# scoutmakes_robot_kit.net
KiCad netlist of a schematic drawn in EAGLE
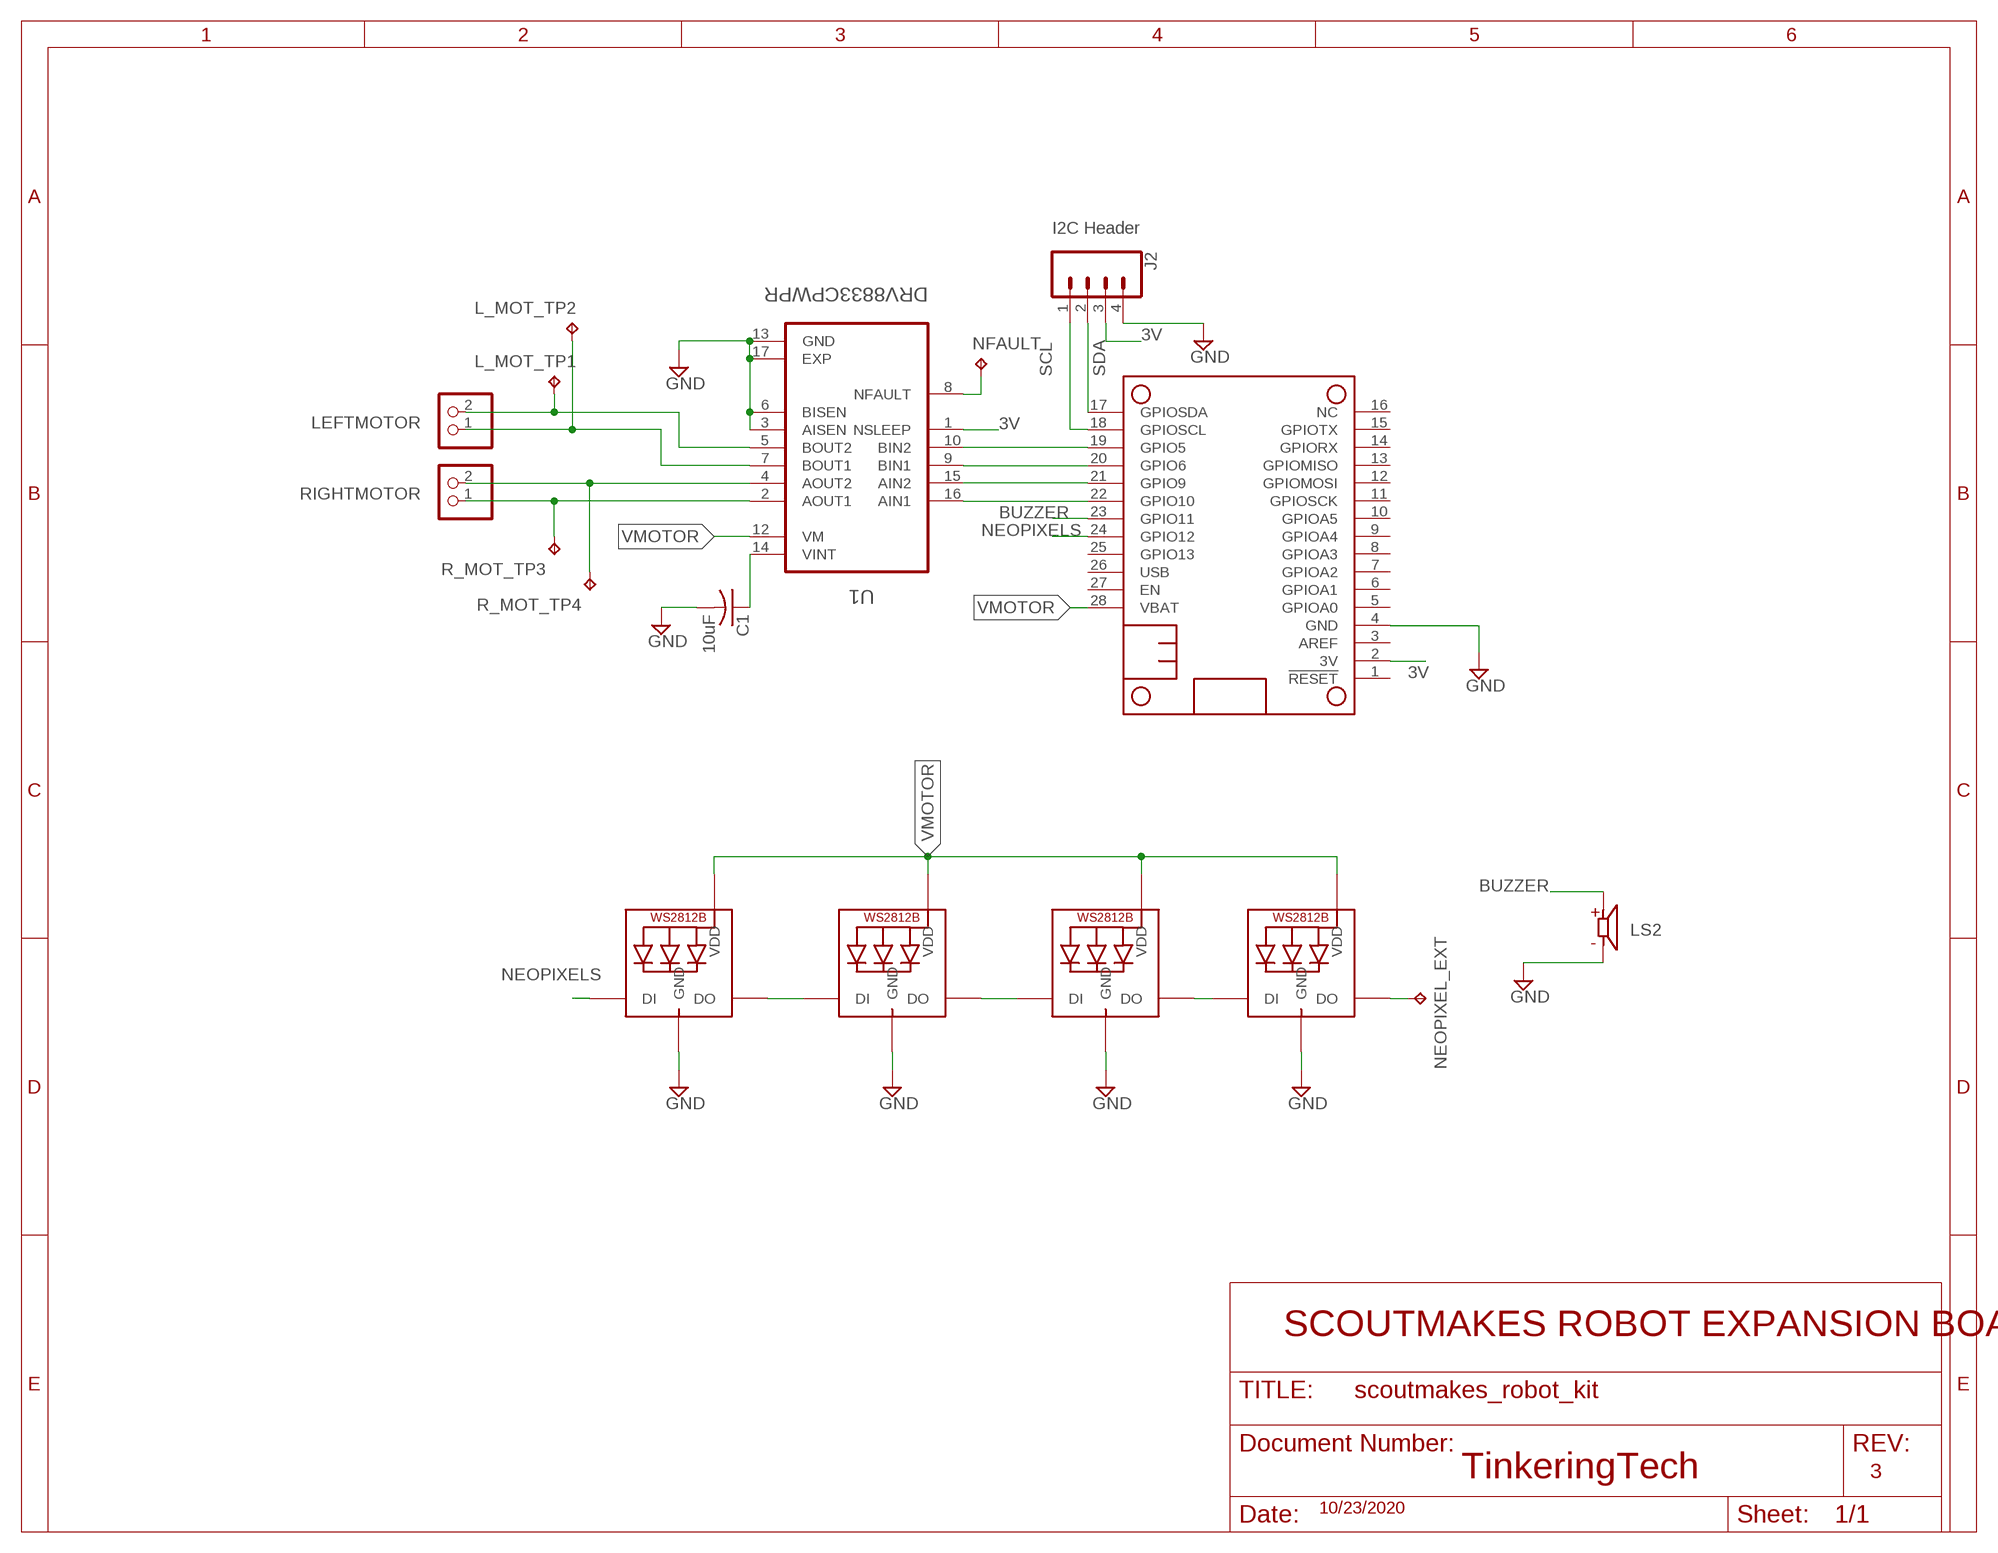
[diagram p0: schematic, sheet 1]

(export (version "E")
  (design (tool "Eeschema 10.0.6"))
  (components
    (comp (ref "C1")
      (value "10uF")
      (footprint "eagle-import:C0805")
      (libsource (lib "eagle-import") (part "C-USC0805"))
    )
    (comp (ref "J2")
      (value "CONN_04")
      (footprint "eagle-import:1X04")
      (libsource (lib "eagle-import") (part "CONN_04"))
    )
    (comp (ref "LED1")
      (value "WS2812B_4020")
      (footprint "eagle-import:WS2812B_4020")
      (libsource (lib "eagle-import") (part "WS2812B_4020"))
    )
    (comp (ref "LED2")
      (value "WS2812B_4020")
      (footprint "eagle-import:WS2812B_4020")
      (libsource (lib "eagle-import") (part "WS2812B_4020"))
    )
    (comp (ref "LED3")
      (value "WS2812B_4020")
      (footprint "eagle-import:WS2812B_4020")
      (libsource (lib "eagle-import") (part "WS2812B_4020"))
    )
    (comp (ref "LED4")
      (value "WS2812B_4020")
      (footprint "eagle-import:WS2812B_4020")
      (libsource (lib "eagle-import") (part "WS2812B_4020"))
    )
    (comp (ref "LEFTMOTOR")
      (value "JSTPH")
      (footprint "eagle-import:JSTPH2")
      (libsource (lib "eagle-import") (part "CON_JST_PH_2PIN"))
    )
    (comp (ref "LS2")
      (value "PKMCS0909E4000-R1")
      (footprint "eagle-import:SPKR_PKMCS0909E4000-R1")
      (fields (field (name "MF") "Murata"))
      (libsource (lib "eagle-import") (part "PKMCS0909E4000-R1"))
    )
    (comp (ref "L_MOT_TP1")
      (value "TPTP09R")
      (footprint "eagle-import:TP09R")
      (libsource (lib "eagle-import") (part "TPTP09R"))
    )
    (comp (ref "L_MOT_TP2")
      (value "TPTP09R")
      (footprint "eagle-import:TP09R")
      (libsource (lib "eagle-import") (part "TPTP09R"))
    )
    (comp (ref "MS2")
      (value "FEATHERWING_NODIM")
      (footprint "eagle-import:FEATHERWING_DIM")
      (libsource (lib "eagle-import") (part "FEATHERWING_NODIM"))
    )
    (comp (ref "NEOPIXEL_EXT")
      (value "TPTP09R")
      (footprint "eagle-import:TP09R")
      (libsource (lib "eagle-import") (part "TPTP09R"))
    )
    (comp (ref "NFAULT")
      (value "TPTP09R")
      (footprint "eagle-import:TP09R")
      (libsource (lib "eagle-import") (part "TPTP09R"))
    )
    (comp (ref "RIGHTMOTOR")
      (value "JSTPH")
      (footprint "eagle-import:JSTPH2")
      (libsource (lib "eagle-import") (part "CON_JST_PH_2PIN"))
    )
    (comp (ref "R_MOT_TP3")
      (value "TPTP09R")
      (footprint "eagle-import:TP09R")
      (libsource (lib "eagle-import") (part "TPTP09R"))
    )
    (comp (ref "R_MOT_TP4")
      (value "TPTP09R")
      (footprint "eagle-import:TP09R")
      (libsource (lib "eagle-import") (part "TPTP09R"))
    )
    (comp (ref "U1")
      (value "DRV8833CPWPR")
      (footprint "eagle-import:SOP65P640X120-17N")
      (fields (field (name "MF") "Texas Instruments"))
      (libsource (lib "eagle-import") (part "DRV8833CPWPR"))
    )
  )
  (nets
    (net (code "1") (name "/3V") (class "Default")
      (node (ref "J2") (pin "3") (pinfunction "3_3") (pintype "passive"))
      (node (ref "MS2") (pin "2") (pinfunction "3V_2") (pintype "power_in"))
      (node (ref "U1") (pin "1") (pinfunction "NSLEEP_1") (pintype "input"))
    )
    (net (code "2") (name "/BUZZER") (class "Default")
      (node (ref "LS2") (pin "1") (pinfunction "P_1") (pintype "passive"))
      (node (ref "MS2") (pin "23") (pinfunction "GPIO11_23") (pintype "bidirectional"))
    )
    (net (code "3") (name "/NEOPIXELS") (class "Default")
      (node (ref "LED1") (pin "1") (pinfunction "DI_1") (pintype "input"))
      (node (ref "MS2") (pin "24") (pinfunction "GPIO12_24") (pintype "bidirectional"))
    )
    (net (code "4") (name "/SCL") (class "Default")
      (node (ref "J2") (pin "1") (pinfunction "1_1") (pintype "passive"))
      (node (ref "MS2") (pin "18") (pinfunction "GPIOSCL_18") (pintype "bidirectional"))
    )
    (net (code "5") (name "/SDA") (class "Default")
      (node (ref "J2") (pin "2") (pinfunction "2_2") (pintype "passive"))
      (node (ref "MS2") (pin "17") (pinfunction "GPIOSDA_17") (pintype "bidirectional"))
    )
    (net (code "6") (name "/USB") (class "Default")
      (node (ref "MS2") (pin "26") (pinfunction "USB_26") (pintype "power_in"))
    )
    (net (code "7") (name "GND") (class "Default")
      (node (ref "C1") (pin "2") (pinfunction "2_2") (pintype "passive"))
      (node (ref "J2") (pin "4") (pinfunction "4_4") (pintype "passive"))
      (node (ref "LED1") (pin "4") (pinfunction "GND_4") (pintype "power_in"))
      (node (ref "LED2") (pin "4") (pinfunction "GND_4") (pintype "power_in"))
      (node (ref "LED3") (pin "4") (pinfunction "GND_4") (pintype "power_in"))
      (node (ref "LED4") (pin "4") (pinfunction "GND_4") (pintype "power_in"))
      (node (ref "LS2") (pin "2") (pinfunction "N_2") (pintype "passive"))
      (node (ref "MS2") (pin "4") (pinfunction "GND_4") (pintype "power_in"))
      (node (ref "U1") (pin "13") (pinfunction "GND_13") (pintype "power_in"))
      (node (ref "U1") (pin "17") (pinfunction "EXP_17") (pintype "power_in"))
      (node (ref "U1") (pin "3") (pinfunction "AISEN_3") (pintype "output"))
      (node (ref "U1") (pin "6") (pinfunction "BISEN_6") (pintype "output"))
    )
    (net (code "8") (name "Net-(LED1-DO)") (class "Default")
      (node (ref "LED1") (pin "3") (pinfunction "DO_3") (pintype "output"))
      (node (ref "LED2") (pin "1") (pinfunction "DI_1") (pintype "input"))
    )
    (net (code "9") (name "Net-(LED2-DO)") (class "Default")
      (node (ref "LED2") (pin "3") (pinfunction "DO_3") (pintype "output"))
      (node (ref "LED3") (pin "1") (pinfunction "DI_1") (pintype "input"))
    )
    (net (code "10") (name "Net-(LED3-DO)") (class "Default")
      (node (ref "LED3") (pin "3") (pinfunction "DO_3") (pintype "output"))
      (node (ref "LED4") (pin "1") (pinfunction "DI_1") (pintype "input"))
    )
    (net (code "11") (name "Net-(LED4-DO)") (class "Default")
      (node (ref "LED4") (pin "3") (pinfunction "DO_3") (pintype "output"))
      (node (ref "NEOPIXEL_EXT") (pin "TP") (pinfunction "TP_TP") (pintype "input"))
    )
    (net (code "12") (name "Net-(MS2-GPIO5)") (class "Default")
      (node (ref "MS2") (pin "19") (pinfunction "GPIO5_19") (pintype "bidirectional"))
      (node (ref "U1") (pin "10") (pinfunction "BIN2_10") (pintype "input"))
    )
    (net (code "13") (name "Net-(MS2-GPIO6)") (class "Default")
      (node (ref "MS2") (pin "20") (pinfunction "GPIO6_20") (pintype "bidirectional"))
      (node (ref "U1") (pin "9") (pinfunction "BIN1_9") (pintype "input"))
    )
    (net (code "14") (name "Net-(MS2-GPIO9)") (class "Default")
      (node (ref "MS2") (pin "21") (pinfunction "GPIO9_21") (pintype "bidirectional"))
      (node (ref "U1") (pin "15") (pinfunction "AIN2_15") (pintype "input"))
    )
    (net (code "15") (name "Net-(MS2-GPIO10)") (class "Default")
      (node (ref "MS2") (pin "22") (pinfunction "GPIO10_22") (pintype "bidirectional"))
      (node (ref "U1") (pin "16") (pinfunction "AIN1_16") (pintype "input"))
    )
    (net (code "16") (name "Net-(U1-AOUT1)") (class "Default")
      (node (ref "RIGHTMOTOR") (pin "1") (pinfunction "1_1") (pintype "passive"))
      (node (ref "R_MOT_TP3") (pin "TP") (pinfunction "TP_TP") (pintype "input"))
      (node (ref "U1") (pin "2") (pinfunction "AOUT1_2") (pintype "output"))
    )
    (net (code "17") (name "Net-(U1-AOUT2)") (class "Default")
      (node (ref "RIGHTMOTOR") (pin "2") (pinfunction "2_2") (pintype "passive"))
      (node (ref "R_MOT_TP4") (pin "TP") (pinfunction "TP_TP") (pintype "input"))
      (node (ref "U1") (pin "4") (pinfunction "AOUT2_4") (pintype "output"))
    )
    (net (code "18") (name "Net-(U1-BOUT1)") (class "Default")
      (node (ref "LEFTMOTOR") (pin "1") (pinfunction "1_1") (pintype "passive"))
      (node (ref "L_MOT_TP2") (pin "TP") (pinfunction "TP_TP") (pintype "input"))
      (node (ref "U1") (pin "7") (pinfunction "BOUT1_7") (pintype "output"))
    )
    (net (code "19") (name "Net-(U1-BOUT2)") (class "Default")
      (node (ref "LEFTMOTOR") (pin "2") (pinfunction "2_2") (pintype "passive"))
      (node (ref "L_MOT_TP1") (pin "TP") (pinfunction "TP_TP") (pintype "input"))
      (node (ref "U1") (pin "5") (pinfunction "BOUT2_5") (pintype "output"))
    )
    (net (code "20") (name "Net-(U1-NFAULT)") (class "Default")
      (node (ref "NFAULT") (pin "TP") (pinfunction "TP_TP") (pintype "input"))
      (node (ref "U1") (pin "8") (pinfunction "NFAULT_8") (pintype "passive"))
    )
    (net (code "21") (name "Net-(U1-VINT)") (class "Default")
      (node (ref "C1") (pin "1") (pinfunction "1_1") (pintype "passive"))
      (node (ref "U1") (pin "14") (pinfunction "VINT_14") (pintype "power_in"))
    )
    (net (code "22") (name "VMOTOR") (class "Default")
      (node (ref "LED1") (pin "2") (pinfunction "VDD_2") (pintype "power_in"))
      (node (ref "LED2") (pin "2") (pinfunction "VDD_2") (pintype "power_in"))
      (node (ref "LED3") (pin "2") (pinfunction "VDD_2") (pintype "power_in"))
      (node (ref "LED4") (pin "2") (pinfunction "VDD_2") (pintype "power_in"))
      (node (ref "MS2") (pin "28") (pinfunction "VBAT_28") (pintype "power_in"))
      (node (ref "U1") (pin "12") (pinfunction "VM_12") (pintype "power_in"))
    )
    (net (code "23") (name "unconnected-(MS2-AREF-Pad3)") (class "Default")
      (node (ref "MS2") (pin "3") (pinfunction "AREF_3") (pintype "passive"))
    )
    (net (code "24") (name "unconnected-(MS2-EN-Pad27)") (class "Default")
      (node (ref "MS2") (pin "27") (pinfunction "EN_27") (pintype "passive"))
    )
    (net (code "25") (name "unconnected-(MS2-GPIO13-Pad25)") (class "Default")
      (node (ref "MS2") (pin "25") (pinfunction "GPIO13_25") (pintype "bidirectional"))
    )
    (net (code "26") (name "unconnected-(MS2-GPIOA0-Pad5)") (class "Default")
      (node (ref "MS2") (pin "5") (pinfunction "GPIOA0_5") (pintype "bidirectional"))
    )
    (net (code "27") (name "unconnected-(MS2-GPIOA1-Pad6)") (class "Default")
      (node (ref "MS2") (pin "6") (pinfunction "GPIOA1_6") (pintype "bidirectional"))
    )
    (net (code "28") (name "unconnected-(MS2-GPIOA2-Pad7)") (class "Default")
      (node (ref "MS2") (pin "7") (pinfunction "GPIOA2_7") (pintype "bidirectional"))
    )
    (net (code "29") (name "unconnected-(MS2-GPIOA3-Pad8)") (class "Default")
      (node (ref "MS2") (pin "8") (pinfunction "GPIOA3_8") (pintype "bidirectional"))
    )
    (net (code "30") (name "unconnected-(MS2-GPIOA4-Pad9)") (class "Default")
      (node (ref "MS2") (pin "9") (pinfunction "GPIOA4_9") (pintype "bidirectional"))
    )
    (net (code "31") (name "unconnected-(MS2-GPIOA5-Pad10)") (class "Default")
      (node (ref "MS2") (pin "10") (pinfunction "GPIOA5_10") (pintype "bidirectional"))
    )
    (net (code "32") (name "unconnected-(MS2-GPIOMISO-Pad13)") (class "Default")
      (node (ref "MS2") (pin "13") (pinfunction "GPIOMISO_13") (pintype "bidirectional"))
    )
    (net (code "33") (name "unconnected-(MS2-GPIOMOSI-Pad12)") (class "Default")
      (node (ref "MS2") (pin "12") (pinfunction "GPIOMOSI_12") (pintype "bidirectional"))
    )
    (net (code "34") (name "unconnected-(MS2-GPIORX-Pad14)") (class "Default")
      (node (ref "MS2") (pin "14") (pinfunction "GPIORX_14") (pintype "bidirectional"))
    )
    (net (code "35") (name "unconnected-(MS2-GPIOSCK-Pad11)") (class "Default")
      (node (ref "MS2") (pin "11") (pinfunction "GPIOSCK_11") (pintype "bidirectional"))
    )
    (net (code "36") (name "unconnected-(MS2-GPIOTX-Pad15)") (class "Default")
      (node (ref "MS2") (pin "15") (pinfunction "GPIOTX_15") (pintype "bidirectional"))
    )
    (net (code "37") (name "unconnected-(MS2-NC-Pad16)") (class "Default")
      (node (ref "MS2") (pin "16") (pinfunction "NC_16") (pintype "passive"))
    )
    (net (code "38") (name "unconnected-(MS2-~{RESET}-Pad1)") (class "Default")
      (node (ref "MS2") (pin "1") (pinfunction "~{RESET}_1") (pintype "input"))
    )
  )
)
